# GhostbustersR1.net
KiCad netlist of a schematic drawn in EAGLE
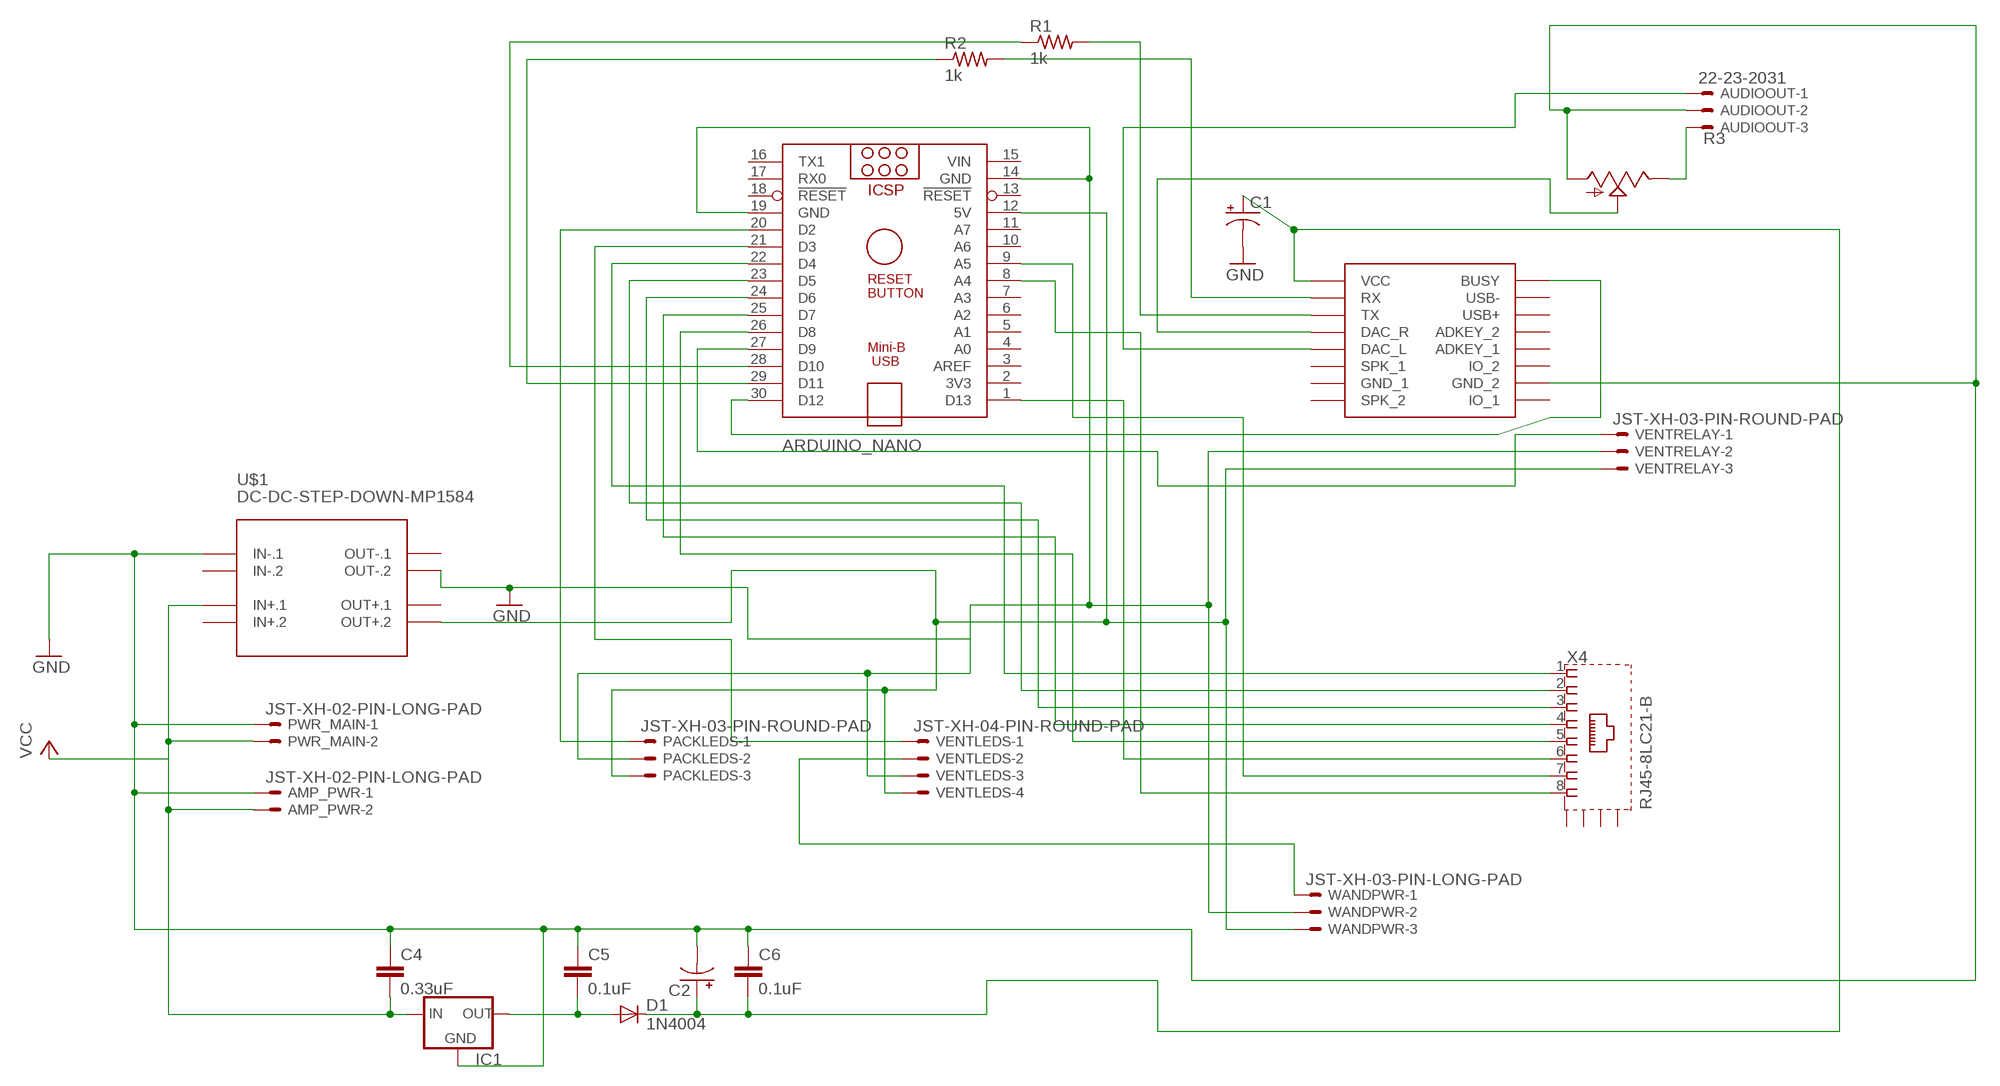
[diagram p0: schematic, sheet 1]

(export (version "E")
  (design (tool "Eeschema 10.0.6"))
  (components
    (comp (ref "AMP_PWR")
      (value "JST-XH-02-PIN-LONG-PAD")
      (footprint "eagle-import:JST-XH-02-PACKAGE-LONG-PAD")
      (libsource (lib "eagle-import") (part "JST-XH-02-PIN-LONG-PAD"))
    )
    (comp (ref "ARDUINO_NANO")
      (value "ARDUINO_NANO")
      (footprint "eagle-import:ARDUINO_NANO")
      (libsource (lib "eagle-import") (part "ARDUINO_NANO"))
    )
    (comp (ref "AUDIOOUT")
      (value "22-23-2031")
      (footprint "eagle-import:22-23-2031")
      (fields (field (name "MF") "MOLEX"))
      (libsource (lib "eagle-import") (part "22-23-2031"))
    )
    (comp (ref "C1")
      (value "CPOL-USE3.5-8")
      (footprint "eagle-import:E3,5-8")
      (libsource (lib "eagle-import") (part "CPOL-USE3.5-8"))
    )
    (comp (ref "C2")
      (value "CPOL-USE3.5-8")
      (footprint "eagle-import:E3,5-8")
      (libsource (lib "eagle-import") (part "CPOL-USE3.5-8"))
    )
    (comp (ref "C4")
      (value "0.33uF")
      (footprint "eagle-import:C2.5-4")
      (libsource (lib "eagle-import") (part "C2.5/4"))
    )
    (comp (ref "C5")
      (value "0.1uF")
      (footprint "eagle-import:C2.5-4")
      (libsource (lib "eagle-import") (part "C2.5/4"))
    )
    (comp (ref "C6")
      (value "0.1uF")
      (footprint "eagle-import:C2.5-4")
      (libsource (lib "eagle-import") (part "C2.5/4"))
    )
    (comp (ref "D1")
      (value "1N4004")
      (footprint "eagle-import:DO41-10")
      (libsource (lib "eagle-import") (part "1N4004"))
    )
    (comp (ref "DFPLAYER")
      (value "DFPLAYER")
      (footprint "eagle-import:DFPLAYER")
      (libsource (lib "eagle-import") (part "DFPLAYER"))
    )
    (comp (ref "IC1")
      (value "78MXXS")
      (footprint "eagle-import:78MXXS")
      (libsource (lib "eagle-import") (part "78MXXS"))
    )
    (comp (ref "PACKLEDS")
      (value "JST-XH-03-PIN-ROUND-PAD")
      (footprint "eagle-import:JST-XH-03-PACKAGE-ROUND-PAD")
      (libsource (lib "eagle-import") (part "JST-XH-03-PIN-ROUND-PAD"))
    )
    (comp (ref "PWR_MAIN")
      (value "JST-XH-02-PIN-LONG-PAD")
      (footprint "eagle-import:JST-XH-02-PACKAGE-LONG-PAD")
      (libsource (lib "eagle-import") (part "JST-XH-02-PIN-LONG-PAD"))
    )
    (comp (ref "R1")
      (value "1k")
      (footprint "eagle-import:0207_12")
      (libsource (lib "eagle-import") (part "R-US_0207/12"))
    )
    (comp (ref "R2")
      (value "1k")
      (footprint "eagle-import:0207_12")
      (libsource (lib "eagle-import") (part "R-US_0207/12"))
    )
    (comp (ref "R3")
      (value "TRIM_US-B64Y")
      (footprint "eagle-import:B64Y")
      (libsource (lib "eagle-import") (part "TRIM_US-B64Y"))
    )
    (comp (ref "U$1")
      (value "DC-DC-STEP-DOWN-MP1584")
      (footprint "eagle-import:DC-DC-STEP-DOWN-MP1584")
      (libsource (lib "eagle-import") (part "DC-DC-STEP-DOWN-MP1584"))
    )
    (comp (ref "VENTLEDS")
      (value "JST-XH-04-PIN-ROUND-PAD")
      (footprint "eagle-import:JST-XH-04-PACKAGE-ROUND-PAD")
      (libsource (lib "eagle-import") (part "JST-XH-04-PIN-ROUND-PAD"))
    )
    (comp (ref "VENTRELAY")
      (value "JST-XH-03-PIN-ROUND-PAD")
      (footprint "eagle-import:JST-XH-03-PACKAGE-ROUND-PAD")
      (libsource (lib "eagle-import") (part "JST-XH-03-PIN-ROUND-PAD"))
    )
    (comp (ref "WANDPWR")
      (value "JST-XH-03-PIN-LONG-PAD")
      (footprint "eagle-import:JST-XH-03-PACKAGE-LONG-PAD")
      (libsource (lib "eagle-import") (part "JST-XH-03-PIN-LONG-PAD"))
    )
    (comp (ref "X4")
      (value "RJ45-8LC21-B")
      (footprint "eagle-import:RJ45-SHIELD1")
      (libsource (lib "eagle-import") (part "RJ4521-B-8LC"))
    )
  )
  (nets
    (net (code "1") (name "/VIN") (class "Default")
      (node (ref "ARDUINO_NANO") (pin "15") (pinfunction "VIN_15") (pintype "power_in"))
    )
    (net (code "2") (name "GND") (class "Default")
      (node (ref "AMP_PWR") (pin "1") (pinfunction "S_1") (pintype "passive"))
      (node (ref "ARDUINO_NANO") (pin "14") (pinfunction "GND_14") (pintype "power_in"))
      (node (ref "ARDUINO_NANO") (pin "19") (pinfunction "GND_19") (pintype "power_in"))
      (node (ref "AUDIOOUT") (pin "2") (pinfunction "S_2") (pintype "passive"))
      (node (ref "C1") (pin "-") (pinfunction "-_-") (pintype "passive"))
      (node (ref "C2") (pin "-") (pinfunction "-_-") (pintype "passive"))
      (node (ref "C4") (pin "1") (pinfunction "1_1") (pintype "passive"))
      (node (ref "C5") (pin "1") (pinfunction "1_1") (pintype "passive"))
      (node (ref "C6") (pin "1") (pinfunction "1_1") (pintype "passive"))
      (node (ref "DFPLAYER") (pin "GND_2") (pinfunction "GND_2_GND_2") (pintype "bidirectional"))
      (node (ref "IC1") (pin "GND") (pinfunction "GND_GND") (pintype "input"))
      (node (ref "PACKLEDS") (pin "2") (pinfunction "S_2") (pintype "passive"))
      (node (ref "PWR_MAIN") (pin "1") (pinfunction "S_1") (pintype "passive"))
      (node (ref "R3") (pin "A") (pinfunction "A_A") (pintype "passive"))
      (node (ref "U$1") (pin "IN-.1") (pinfunction "IN-.1_IN-.1") (pintype "bidirectional"))
      (node (ref "U$1") (pin "OUT-.2") (pinfunction "OUT-.2_OUT-.2") (pintype "bidirectional"))
      (node (ref "VENTLEDS") (pin "3") (pinfunction "S_3") (pintype "passive"))
      (node (ref "VENTRELAY") (pin "2") (pinfunction "S_2") (pintype "passive"))
      (node (ref "WANDPWR") (pin "2") (pinfunction "S_2") (pintype "passive"))
    )
    (net (code "3") (name "Net-(ARDUINO_NANO-5V)") (class "Default")
      (node (ref "ARDUINO_NANO") (pin "12") (pinfunction "5V_12") (pintype "power_in"))
      (node (ref "PACKLEDS") (pin "3") (pinfunction "S_3") (pintype "passive"))
      (node (ref "U$1") (pin "OUT+.2") (pinfunction "OUT+.2_OUT+.2") (pintype "bidirectional"))
      (node (ref "VENTLEDS") (pin "4") (pinfunction "S_4") (pintype "passive"))
      (node (ref "VENTRELAY") (pin "3") (pinfunction "S_3") (pintype "passive"))
      (node (ref "WANDPWR") (pin "3") (pinfunction "S_3") (pintype "passive"))
    )
    (net (code "4") (name "Net-(ARDUINO_NANO-A4)") (class "Default")
      (node (ref "ARDUINO_NANO") (pin "8") (pinfunction "A4_8") (pintype "bidirectional"))
      (node (ref "X4") (pin "8") (pinfunction "8_8") (pintype "passive"))
    )
    (net (code "5") (name "Net-(ARDUINO_NANO-A5)") (class "Default")
      (node (ref "ARDUINO_NANO") (pin "9") (pinfunction "A5_9") (pintype "bidirectional"))
      (node (ref "X4") (pin "7") (pinfunction "7_7") (pintype "passive"))
    )
    (net (code "6") (name "Net-(ARDUINO_NANO-D2)") (class "Default")
      (node (ref "ARDUINO_NANO") (pin "20") (pinfunction "D2_20") (pintype "bidirectional"))
      (node (ref "PACKLEDS") (pin "1") (pinfunction "S_1") (pintype "passive"))
    )
    (net (code "7") (name "Net-(ARDUINO_NANO-D3)") (class "Default")
      (node (ref "ARDUINO_NANO") (pin "21") (pinfunction "D3_21") (pintype "bidirectional"))
      (node (ref "VENTLEDS") (pin "1") (pinfunction "S_1") (pintype "passive"))
    )
    (net (code "8") (name "Net-(ARDUINO_NANO-D4)") (class "Default")
      (node (ref "ARDUINO_NANO") (pin "22") (pinfunction "D4_22") (pintype "bidirectional"))
      (node (ref "X4") (pin "1") (pinfunction "1_1") (pintype "passive"))
    )
    (net (code "9") (name "Net-(ARDUINO_NANO-D5)") (class "Default")
      (node (ref "ARDUINO_NANO") (pin "23") (pinfunction "D5_23") (pintype "bidirectional"))
      (node (ref "X4") (pin "2") (pinfunction "2_2") (pintype "passive"))
    )
    (net (code "10") (name "Net-(ARDUINO_NANO-D6)") (class "Default")
      (node (ref "ARDUINO_NANO") (pin "24") (pinfunction "D6_24") (pintype "bidirectional"))
      (node (ref "X4") (pin "3") (pinfunction "3_3") (pintype "passive"))
    )
    (net (code "11") (name "Net-(ARDUINO_NANO-D7)") (class "Default")
      (node (ref "ARDUINO_NANO") (pin "25") (pinfunction "D7_25") (pintype "bidirectional"))
      (node (ref "X4") (pin "4") (pinfunction "4_4") (pintype "passive"))
    )
    (net (code "12") (name "Net-(ARDUINO_NANO-D8)") (class "Default")
      (node (ref "ARDUINO_NANO") (pin "26") (pinfunction "D8_26") (pintype "bidirectional"))
      (node (ref "X4") (pin "5") (pinfunction "5_5") (pintype "passive"))
    )
    (net (code "13") (name "Net-(ARDUINO_NANO-D9)") (class "Default")
      (node (ref "ARDUINO_NANO") (pin "27") (pinfunction "D9_27") (pintype "bidirectional"))
      (node (ref "VENTRELAY") (pin "1") (pinfunction "S_1") (pintype "passive"))
    )
    (net (code "14") (name "Net-(ARDUINO_NANO-D10)") (class "Default")
      (node (ref "ARDUINO_NANO") (pin "28") (pinfunction "D10_28") (pintype "bidirectional"))
      (node (ref "R1") (pin "1") (pinfunction "1_1") (pintype "passive"))
    )
    (net (code "15") (name "Net-(ARDUINO_NANO-D11)") (class "Default")
      (node (ref "ARDUINO_NANO") (pin "29") (pinfunction "D11_29") (pintype "bidirectional"))
      (node (ref "R2") (pin "1") (pinfunction "1_1") (pintype "passive"))
    )
    (net (code "16") (name "Net-(ARDUINO_NANO-D12)") (class "Default")
      (node (ref "ARDUINO_NANO") (pin "30") (pinfunction "D12_30") (pintype "bidirectional"))
      (node (ref "DFPLAYER") (pin "BUSY") (pinfunction "BUSY_BUSY") (pintype "bidirectional"))
    )
    (net (code "17") (name "Net-(ARDUINO_NANO-D13)") (class "Default")
      (node (ref "ARDUINO_NANO") (pin "1") (pinfunction "D13_1") (pintype "bidirectional"))
      (node (ref "X4") (pin "6") (pinfunction "6_6") (pintype "passive"))
    )
    (net (code "18") (name "Net-(AUDIOOUTA-S)") (class "Default")
      (node (ref "AUDIOOUT") (pin "1") (pinfunction "S_1") (pintype "passive"))
      (node (ref "DFPLAYER") (pin "DAC_L") (pinfunction "DAC_L_DAC_L") (pintype "bidirectional"))
    )
    (net (code "19") (name "Net-(AUDIOOUTC-S)") (class "Default")
      (node (ref "AUDIOOUT") (pin "3") (pinfunction "S_3") (pintype "passive"))
      (node (ref "R3") (pin "E") (pinfunction "E_E") (pintype "passive"))
    )
    (net (code "20") (name "Net-(C1-Pad+)") (class "Default")
      (node (ref "C1") (pin "+") (pinfunction "+_+") (pintype "passive"))
      (node (ref "C2") (pin "+") (pinfunction "+_+") (pintype "passive"))
      (node (ref "C6") (pin "2") (pinfunction "2_2") (pintype "passive"))
      (node (ref "D1") (pin "C") (pinfunction "C_C") (pintype "passive"))
      (node (ref "DFPLAYER") (pin "VCC") (pinfunction "VCC_VCC") (pintype "bidirectional"))
    )
    (net (code "21") (name "Net-(C5-Pad2)") (class "Default")
      (node (ref "C5") (pin "2") (pinfunction "2_2") (pintype "passive"))
      (node (ref "D1") (pin "A") (pinfunction "A_A") (pintype "passive"))
      (node (ref "IC1") (pin "OUT") (pinfunction "OUT_OUT") (pintype "passive"))
    )
    (net (code "22") (name "Net-(DFPLAYER-PadDAC_R)") (class "Default")
      (node (ref "DFPLAYER") (pin "DAC_R") (pinfunction "DAC_R_DAC_R") (pintype "bidirectional"))
      (node (ref "R3") (pin "S") (pinfunction "S_S") (pintype "passive"))
    )
    (net (code "23") (name "Net-(DFPLAYER-PadRX)") (class "Default")
      (node (ref "DFPLAYER") (pin "RX") (pinfunction "RX_RX") (pintype "bidirectional"))
      (node (ref "R2") (pin "2") (pinfunction "2_2") (pintype "passive"))
    )
    (net (code "24") (name "Net-(DFPLAYER-PadTX)") (class "Default")
      (node (ref "DFPLAYER") (pin "TX") (pinfunction "TX_TX") (pintype "bidirectional"))
      (node (ref "R1") (pin "2") (pinfunction "2_2") (pintype "passive"))
    )
    (net (code "25") (name "Net-(VENTLEDSB-S)") (class "Default")
      (node (ref "VENTLEDS") (pin "2") (pinfunction "S_2") (pintype "passive"))
      (node (ref "WANDPWR") (pin "1") (pinfunction "S_1") (pintype "passive"))
    )
    (net (code "26") (name "VCC") (class "Default")
      (node (ref "AMP_PWR") (pin "2") (pinfunction "S_2") (pintype "passive"))
      (node (ref "C4") (pin "2") (pinfunction "2_2") (pintype "passive"))
      (node (ref "IC1") (pin "IN") (pinfunction "IN_IN") (pintype "input"))
      (node (ref "PWR_MAIN") (pin "2") (pinfunction "S_2") (pintype "passive"))
      (node (ref "U$1") (pin "IN+.1") (pinfunction "IN+.1_IN+.1") (pintype "bidirectional"))
    )
    (net (code "27") (name "unconnected-(ARDUINO_NANO-3V3-Pad2)") (class "Default")
      (node (ref "ARDUINO_NANO") (pin "2") (pinfunction "3V3_2") (pintype "output"))
    )
    (net (code "28") (name "unconnected-(ARDUINO_NANO-A0-Pad4)") (class "Default")
      (node (ref "ARDUINO_NANO") (pin "4") (pinfunction "A0_4") (pintype "bidirectional"))
    )
    (net (code "29") (name "unconnected-(ARDUINO_NANO-A1-Pad5)") (class "Default")
      (node (ref "ARDUINO_NANO") (pin "5") (pinfunction "A1_5") (pintype "bidirectional"))
    )
    (net (code "30") (name "unconnected-(ARDUINO_NANO-A2-Pad6)") (class "Default")
      (node (ref "ARDUINO_NANO") (pin "6") (pinfunction "A2_6") (pintype "bidirectional"))
    )
    (net (code "31") (name "unconnected-(ARDUINO_NANO-A3-Pad7)") (class "Default")
      (node (ref "ARDUINO_NANO") (pin "7") (pinfunction "A3_7") (pintype "bidirectional"))
    )
    (net (code "32") (name "unconnected-(ARDUINO_NANO-A6-Pad10)") (class "Default")
      (node (ref "ARDUINO_NANO") (pin "10") (pinfunction "A6_10") (pintype "bidirectional"))
    )
    (net (code "33") (name "unconnected-(ARDUINO_NANO-A7-Pad11)") (class "Default")
      (node (ref "ARDUINO_NANO") (pin "11") (pinfunction "A7_11") (pintype "bidirectional"))
    )
    (net (code "34") (name "unconnected-(ARDUINO_NANO-AREF-Pad3)") (class "Default")
      (node (ref "ARDUINO_NANO") (pin "3") (pinfunction "AREF_3") (pintype "input"))
    )
    (net (code "35") (name "unconnected-(ARDUINO_NANO-RX0-Pad17)") (class "Default")
      (node (ref "ARDUINO_NANO") (pin "17") (pinfunction "RX0_17") (pintype "bidirectional"))
    )
    (net (code "36") (name "unconnected-(ARDUINO_NANO-TX1-Pad16)") (class "Default")
      (node (ref "ARDUINO_NANO") (pin "16") (pinfunction "TX1_16") (pintype "bidirectional"))
    )
    (net (code "37") (name "unconnected-(ARDUINO_NANO-~{RESET}-Pad13)") (class "Default")
      (node (ref "ARDUINO_NANO") (pin "13") (pinfunction "~{RESET}_13") (pintype "input"))
    )
    (net (code "38") (name "unconnected-(ARDUINO_NANO-~{RESET}-Pad18)") (class "Default")
      (node (ref "ARDUINO_NANO") (pin "18") (pinfunction "~{RESET}_18") (pintype "input"))
    )
    (net (code "39") (name "unconnected-(DFPLAYER-ADKEY_1-PadADKEY1)") (class "Default")
      (node (ref "DFPLAYER") (pin "ADKEY1") (pinfunction "ADKEY_1_ADKEY1") (pintype "bidirectional"))
    )
    (net (code "40") (name "unconnected-(DFPLAYER-ADKEY_2-PadADKEY2)") (class "Default")
      (node (ref "DFPLAYER") (pin "ADKEY2") (pinfunction "ADKEY_2_ADKEY2") (pintype "bidirectional"))
    )
    (net (code "41") (name "unconnected-(DFPLAYER-IO_1-PadIO1)") (class "Default")
      (node (ref "DFPLAYER") (pin "IO1") (pinfunction "IO_1_IO1") (pintype "bidirectional"))
    )
    (net (code "42") (name "unconnected-(DFPLAYER-IO_2-PadIO2)") (class "Default")
      (node (ref "DFPLAYER") (pin "IO2") (pinfunction "IO_2_IO2") (pintype "bidirectional"))
    )
    (net (code "43") (name "unconnected-(DFPLAYER-PadGND_1)") (class "Default")
      (node (ref "DFPLAYER") (pin "GND_1") (pinfunction "GND_1_GND_1") (pintype "bidirectional"))
    )
    (net (code "44") (name "unconnected-(DFPLAYER-PadUSB+)") (class "Default")
      (node (ref "DFPLAYER") (pin "USB+") (pinfunction "USB+_USB+") (pintype "bidirectional"))
    )
    (net (code "45") (name "unconnected-(DFPLAYER-PadUSB-)") (class "Default")
      (node (ref "DFPLAYER") (pin "USB-") (pinfunction "USB-_USB-") (pintype "bidirectional"))
    )
    (net (code "46") (name "unconnected-(DFPLAYER-SPK_1-PadSPK1)") (class "Default")
      (node (ref "DFPLAYER") (pin "SPK1") (pinfunction "SPK_1_SPK1") (pintype "bidirectional"))
    )
    (net (code "47") (name "unconnected-(DFPLAYER-SPK_2-PadSPK2)") (class "Default")
      (node (ref "DFPLAYER") (pin "SPK2") (pinfunction "SPK_2_SPK2") (pintype "bidirectional"))
    )
    (net (code "48") (name "unconnected-(U$1-PadIN+.2)") (class "Default")
      (node (ref "U$1") (pin "IN+.2") (pinfunction "IN+.2_IN+.2") (pintype "bidirectional"))
    )
    (net (code "49") (name "unconnected-(U$1-PadIN-.2)") (class "Default")
      (node (ref "U$1") (pin "IN-.2") (pinfunction "IN-.2_IN-.2") (pintype "bidirectional"))
    )
    (net (code "50") (name "unconnected-(U$1-PadOUT+.1)") (class "Default")
      (node (ref "U$1") (pin "OUT+.1") (pinfunction "OUT+.1_OUT+.1") (pintype "bidirectional"))
    )
    (net (code "51") (name "unconnected-(U$1-PadOUT-.1)") (class "Default")
      (node (ref "U$1") (pin "OUT-.1") (pinfunction "OUT-.1_OUT-.1") (pintype "bidirectional"))
    )
    (net (code "52") (name "unconnected-(X4-S-PadS1)") (class "Default")
      (node (ref "X4") (pin "S1") (pinfunction "S_S1") (pintype "passive"))
    )
    (net (code "53") (name "unconnected-(X4-S-PadS2)") (class "Default")
      (node (ref "X4") (pin "S2") (pinfunction "S_S2") (pintype "passive"))
    )
    (net (code "54") (name "unconnected-(X4-S-PadS3)") (class "Default")
      (node (ref "X4") (pin "S3") (pinfunction "S_S3") (pintype "passive"))
    )
    (net (code "55") (name "unconnected-(X4-S-PadS4)") (class "Default")
      (node (ref "X4") (pin "S4") (pinfunction "S_S4") (pintype "passive"))
    )
  )
)
